# DS130-1_0-A_G-M.net
KiCad netlist of a schematic drawn in Altium Designer
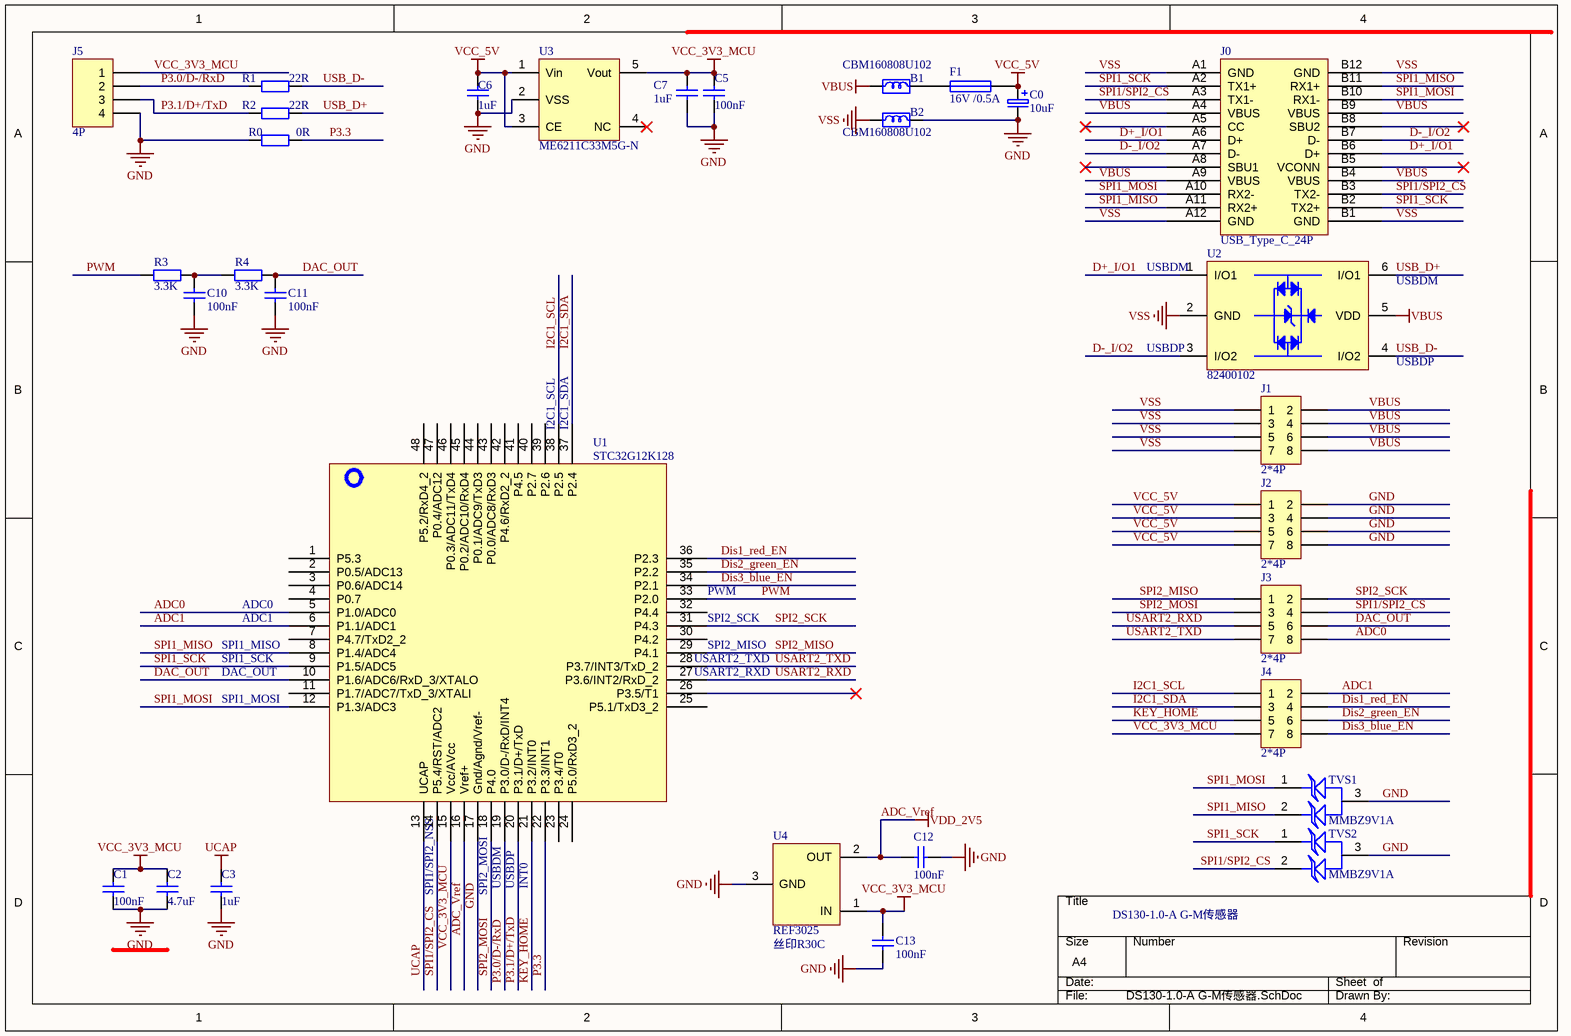
[diagram p0: DS130-1.0-A G-M传感器.SchDoc]

(export (version "E")
  (design (tool "Eeschema 10.0.6"))
  (components
    (comp (ref "B1")
      (value "CBM160808U102")
      (footprint "0603Bead")
      (description "贴片磁珠")
      (libsource (lib "AD_SCH") (part "Chip Ferrite Bead 0606"))
    )
    (comp (ref "B2")
      (value "CBM160808U102")
      (footprint "0603Bead")
      (description "贴片磁珠")
      (libsource (lib "AD_SCH") (part "Chip Ferrite Bead 0606"))
    )
    (comp (ref "C0")
      (value "10uF")
      (footprint "AVX_3216-18(1206)_SMD")
      (description "钽电容")
      (fields (field (name "Comment") "AVX_10uF/16V ±10％(C106)"))
      (libsource (lib "AD_SCH") (part "AVX_10uF/16V ±10％(C106)"))
    )
    (comp (ref "C1")
      (value "100nF")
      (footprint "0603CAP")
      (description "贴片电容")
      (fields (field (name "Comment") "SMDCAP00013"))
      (libsource (lib "AD_SCH") (part "MLCC 100nF 50V ±10％ 0603"))
    )
    (comp (ref "C2")
      (value "4.7uF")
      (footprint "0603CAP")
      (description "贴片电容")
      (fields (field (name "Comment") "SMDCAP00012"))
      (libsource (lib "AD_SCH") (part "MLCC 4.7uF 50V ±10％ 0603"))
    )
    (comp (ref "C3")
      (value "1uF")
      (footprint "0603CAP")
      (description "贴片电容")
      (fields (field (name "Comment") "SMDCAP00015"))
      (libsource (lib "AD_SCH") (part "MLCC 1uF 50V ±10％ 0603"))
    )
    (comp (ref "C5")
      (value "100nF")
      (footprint "0603CAP")
      (description "贴片电容")
      (fields (field (name "Comment") "SMDCAP00013"))
      (libsource (lib "AD_SCH") (part "MLCC 100nF 50V ±10％ 0603"))
    )
    (comp (ref "C6")
      (value "1uF")
      (footprint "0603CAP")
      (description "贴片电容")
      (fields (field (name "Comment") "SMDCAP00015"))
      (libsource (lib "AD_SCH") (part "MLCC 1uF 50V ±10％ 0603"))
    )
    (comp (ref "C7")
      (value "1uF")
      (footprint "0603CAP")
      (description "贴片电容")
      (fields (field (name "Comment") "SMDCAP00015"))
      (libsource (lib "AD_SCH") (part "MLCC 1uF 50V ±10％ 0603"))
    )
    (comp (ref "C10")
      (value "100nF")
      (footprint "0603CAP")
      (description "贴片电容")
      (fields (field (name "Comment") "SMDCAP00013"))
      (libsource (lib "AD_SCH") (part "MLCC 100nF 50V ±10％ 0603"))
    )
    (comp (ref "C11")
      (value "100nF")
      (footprint "0603CAP")
      (description "贴片电容")
      (fields (field (name "Comment") "SMDCAP00013"))
      (libsource (lib "AD_SCH") (part "MLCC 100nF 50V ±10％ 0603"))
    )
    (comp (ref "C12")
      (value "100nF")
      (footprint "0603CAP")
      (description "贴片电容")
      (fields (field (name "Comment") "SMDCAP00013"))
      (libsource (lib "AD_SCH") (part "MLCC 100nF 50V ±10％ 0603"))
    )
    (comp (ref "C13")
      (value "100nF")
      (footprint "0603CAP")
      (description "贴片电容")
      (fields (field (name "Comment") "SMDCAP00013"))
      (libsource (lib "AD_SCH") (part "MLCC 100nF 50V ±10％ 0603"))
    )
    (comp (ref "F1")
      (value "16V /0.5A")
      (footprint "1206FUSE")
      (description "贴片自恢复保险丝 16V /0.5A")
      (fields (field (name "Comment") "SMD1206-050C-16V"))
      (libsource (lib "AD_SCH") (part "SMD1206-050C-16V"))
    )
    (comp (ref "J0")
      (value "USB_Type_C_24P")
      (footprint "USB_TYPE_C_24P_Receptacle")
      (libsource (lib "AD_SCH") (part "USB_Type_C_24P"))
    )
    (comp (ref "J1")
      (value "2*4P")
      (footprint "X1321FVS-2x04-C43D48")
      (description "双排母2x4P 立贴 1.27mm")
      (fields (field (name "Comment") "X1321FVS-2x04-C43D48"))
      (libsource (lib "AD_SCH") (part "X1321FVS-2x04-C43D48"))
    )
    (comp (ref "J2")
      (value "2*4P")
      (footprint "X1321FVS-2x04-C43D48")
      (description "双排母2x4P 立贴 1.27mm")
      (fields (field (name "Comment") "X1321FVS-2x04-C43D48"))
      (libsource (lib "AD_SCH") (part "X1321FVS-2x04-C43D48"))
    )
    (comp (ref "J3")
      (value "2*4P")
      (footprint "X1321FVS-2x04-C43D48")
      (description "双排母2x4P 立贴 1.27mm")
      (fields (field (name "Comment") "X1321FVS-2x04-C43D48"))
      (libsource (lib "AD_SCH") (part "X1321FVS-2x04-C43D48"))
    )
    (comp (ref "J4")
      (value "2*4P")
      (footprint "X1321FVS-2x04-C43D48")
      (description "双排母2x4P 立贴 1.27mm")
      (fields (field (name "Comment") "X1321FVS-2x04-C43D48"))
      (libsource (lib "AD_SCH") (part "X1321FVS-2x04-C43D48"))
    )
    (comp (ref "J5")
      (value "4P")
      (footprint "H4")
      (description "单排直针")
      (fields (field (name "Comment") "DIP4单排直针  间距2mm 针长11mm 铜"))
      (libsource (lib "AD_SCH") (part "DIP4单排直针  间距2mm 针长11mm 铜"))
    )
    (comp (ref "R0")
      (value "0R")
      (footprint "0603RES")
      (description "贴片电阻")
      (fields (field (name "Comment") "Chip 0R 1/16W ±1％ 0603"))
      (libsource (lib "AD_SCH") (part "Chip 0R 1/16W ±1％ 0603"))
    )
    (comp (ref "R1")
      (value "22R")
      (footprint "0603RES")
      (description "贴片电阻")
      (fields (field (name "Comment") "Chip 22R 1/16W ±1％ 0603"))
      (libsource (lib "AD_SCH") (part "Chip 22R 1/16W ±1％ 0603"))
    )
    (comp (ref "R2")
      (value "22R")
      (footprint "0603RES")
      (description "贴片电阻")
      (fields (field (name "Comment") "Chip 22R 1/16W ±1％ 0603"))
      (libsource (lib "AD_SCH") (part "Chip 22R 1/16W ±1％ 0603"))
    )
    (comp (ref "R3")
      (value "3.3K")
      (footprint "0603RES")
      (description "贴片电阻")
      (fields (field (name "Comment") "SMDRES00090"))
      (libsource (lib "AD_SCH") (part "Chip 3.3K 1/16W ±1％ 0603"))
    )
    (comp (ref "R4")
      (value "3.3K")
      (footprint "0603RES")
      (description "贴片电阻")
      (fields (field (name "Comment") "SMDRES00090"))
      (libsource (lib "AD_SCH") (part "Chip 3.3K 1/16W ±1％ 0603"))
    )
    (comp (ref "TVS1")
      (value "MMBZ9V1A")
      (footprint "SOT23")
      (description "瞬态抑制二极管")
      (libsource (lib "AD_SCH") (part "TVS"))
    )
    (comp (ref "TVS2")
      (value "MMBZ9V1A")
      (footprint "SOT23")
      (description "瞬态抑制二极管")
      (libsource (lib "AD_SCH") (part "TVS"))
    )
    (comp (ref "U1")
      (value "STC32G12K128")
      (footprint "LQFP-48")
      (description "单片机芯片")
      (fields (field (name "Comment") "STC32G12K128_35I LQFP48"))
      (libsource (lib "AD_SCH") (part "STC32G12K128_35I LQFP48"))
    )
    (comp (ref "U2")
      (value "82400102")
      (footprint "SOT23-6")
      (description "瞬态抑制二极管(TVS)")
      (libsource (lib "AD_SCH") (part "82400102"))
    )
    (comp (ref "U3")
      (value "ME6211C33M5G-N")
      (footprint "SOT23-5")
      (description "稳压芯片")
      (libsource (lib "AD_SCH") (part "ME6211C33M5G-N"))
    )
    (comp (ref "U4")
      (value "REF3025")
      (footprint "SOT23")
      (fields (field (name "ALTIUM_VALUE") "丝印R30C"))
      (libsource (lib "AD_SCH") (part "REF3025"))
    )
  )
  (nets
    (net (code "1") (name "/ADC0") (class "Default")
      (node (ref "J3") (pin "8") (pinfunction "8_8") (pintype "passive"))
      (node (ref "U1") (pin "5") (pinfunction "P1.0/ADC0_5") (pintype "passive"))
    )
    (net (code "2") (name "/ADC1") (class "Default")
      (node (ref "J4") (pin "2") (pinfunction "2_2") (pintype "passive"))
      (node (ref "U1") (pin "6") (pinfunction "P1.1/ADC1_6") (pintype "passive"))
    )
    (net (code "3") (name "/D+_I{slash}O1") (class "Default")
      (node (ref "J0") (pin "A6") (pinfunction "D+_A6") (pintype "passive"))
      (node (ref "J0") (pin "B6") (pinfunction "D+_B6") (pintype "passive"))
      (node (ref "U2") (pin "1") (pinfunction "I/O1_1") (pintype "passive"))
    )
    (net (code "4") (name "/D-_I{slash}O2") (class "Default")
      (node (ref "J0") (pin "A7") (pinfunction "D-_A7") (pintype "passive"))
      (node (ref "J0") (pin "B7") (pinfunction "D-_B7") (pintype "passive"))
      (node (ref "U2") (pin "3") (pinfunction "I/O2_3") (pintype "passive"))
    )
    (net (code "5") (name "/DAC_OUT") (class "Default")
      (node (ref "C11") (pin "2") (pinfunction "2_2") (pintype "passive"))
      (node (ref "J3") (pin "6") (pinfunction "6_6") (pintype "passive"))
      (node (ref "R4") (pin "2") (pinfunction "2_2") (pintype "passive"))
      (node (ref "U1") (pin "10") (pinfunction "P1.6/ADC6/RxD_3/XTALO_10") (pintype "passive"))
    )
    (net (code "6") (name "/Dis1_red_EN") (class "Default")
      (node (ref "J4") (pin "4") (pinfunction "4_4") (pintype "passive"))
      (node (ref "U1") (pin "36") (pinfunction "P2.3_36") (pintype "passive"))
    )
    (net (code "7") (name "/Dis2_green_EN") (class "Default")
      (node (ref "J4") (pin "6") (pinfunction "6_6") (pintype "passive"))
      (node (ref "U1") (pin "35") (pinfunction "P2.2_35") (pintype "passive"))
    )
    (net (code "8") (name "/Dis3_blue_EN") (class "Default")
      (node (ref "J4") (pin "8") (pinfunction "8_8") (pintype "passive"))
      (node (ref "U1") (pin "34") (pinfunction "P2.1_34") (pintype "passive"))
    )
    (net (code "9") (name "/I2C1_SCL") (class "Default")
      (node (ref "J4") (pin "1") (pinfunction "1_1") (pintype "passive"))
      (node (ref "U1") (pin "38") (pinfunction "P2.5_38") (pintype "passive"))
    )
    (net (code "10") (name "/I2C1_SDA") (class "Default")
      (node (ref "J4") (pin "3") (pinfunction "3_3") (pintype "passive"))
      (node (ref "U1") (pin "37") (pinfunction "P2.4_37") (pintype "passive"))
    )
    (net (code "11") (name "/KEY_HOME") (class "Default")
      (node (ref "J4") (pin "5") (pinfunction "5_5") (pintype "passive"))
      (node (ref "U1") (pin "21") (pinfunction "P3.2/INT0_21") (pintype "passive"))
    )
    (net (code "12") (name "/P3.0{slash}D-{slash}RxD") (class "Default")
      (node (ref "J5") (pin "2") (pinfunction "2_2") (pintype "passive"))
      (node (ref "R1") (pin "1") (pinfunction "1_1") (pintype "passive"))
      (node (ref "U1") (pin "19") (pinfunction "P3.0/D-/RxD/INT4_19") (pintype "passive"))
    )
    (net (code "13") (name "/P3.1{slash}D+{slash}TxD") (class "Default")
      (node (ref "J5") (pin "3") (pinfunction "3_3") (pintype "passive"))
      (node (ref "R2") (pin "1") (pinfunction "1_1") (pintype "passive"))
      (node (ref "U1") (pin "20") (pinfunction "P3.1/D+/TxD_20") (pintype "passive"))
    )
    (net (code "14") (name "/P3.3") (class "Default")
      (node (ref "R0") (pin "2") (pinfunction "2_2") (pintype "passive"))
      (node (ref "U1") (pin "22") (pinfunction "P3.3/INT1_22") (pintype "passive"))
    )
    (net (code "15") (name "/PWM") (class "Default")
      (node (ref "R3") (pin "1") (pinfunction "1_1") (pintype "passive"))
      (node (ref "U1") (pin "33") (pinfunction "P2.0_33") (pintype "passive"))
    )
    (net (code "16") (name "/SPI1_MISO") (class "Default")
      (node (ref "J0") (pin "A11") (pinfunction "RX2+_A11") (pintype "passive"))
      (node (ref "J0") (pin "B11") (pinfunction "RX1+_B11") (pintype "passive"))
      (node (ref "TVS1") (pin "2") (pinfunction "2_2") (pintype "passive"))
      (node (ref "U1") (pin "8") (pinfunction "P1.4/ADC4_8") (pintype "passive"))
    )
    (net (code "17") (name "/SPI1_MOSI") (class "Default")
      (node (ref "J0") (pin "A10") (pinfunction "RX2-_A10") (pintype "passive"))
      (node (ref "J0") (pin "B10") (pinfunction "RX1-_B10") (pintype "passive"))
      (node (ref "TVS1") (pin "1") (pinfunction "1_1") (pintype "passive"))
      (node (ref "U1") (pin "12") (pinfunction "P1.3/ADC3_12") (pintype "passive"))
    )
    (net (code "18") (name "/SPI1_SCK") (class "Default")
      (node (ref "J0") (pin "A2") (pinfunction "TX1+_A2") (pintype "passive"))
      (node (ref "J0") (pin "B2") (pinfunction "TX2+_B2") (pintype "passive"))
      (node (ref "TVS2") (pin "1") (pinfunction "1_1") (pintype "passive"))
      (node (ref "U1") (pin "9") (pinfunction "P1.5/ADC5_9") (pintype "passive"))
    )
    (net (code "19") (name "/SPI1{slash}SPI2_CS") (class "Default")
      (node (ref "J0") (pin "A3") (pinfunction "TX1-_A3") (pintype "passive"))
      (node (ref "J0") (pin "B3") (pinfunction "TX2-_B3") (pintype "passive"))
      (node (ref "J3") (pin "4") (pinfunction "4_4") (pintype "passive"))
      (node (ref "TVS2") (pin "2") (pinfunction "2_2") (pintype "passive"))
      (node (ref "U1") (pin "14") (pinfunction "P5.4/RST/ADC2_14") (pintype "passive"))
    )
    (net (code "20") (name "/SPI2_MISO") (class "Default")
      (node (ref "J3") (pin "1") (pinfunction "1_1") (pintype "passive"))
      (node (ref "U1") (pin "29") (pinfunction "P4.1_29") (pintype "passive"))
    )
    (net (code "21") (name "/SPI2_MOSI") (class "Default")
      (node (ref "J3") (pin "3") (pinfunction "3_3") (pintype "passive"))
      (node (ref "U1") (pin "18") (pinfunction "P4.0_18") (pintype "passive"))
    )
    (net (code "22") (name "/SPI2_SCK") (class "Default")
      (node (ref "J3") (pin "2") (pinfunction "2_2") (pintype "passive"))
      (node (ref "U1") (pin "31") (pinfunction "P4.3_31") (pintype "passive"))
    )
    (net (code "23") (name "/USART2_RXD") (class "Default")
      (node (ref "J3") (pin "5") (pinfunction "5_5") (pintype "passive"))
      (node (ref "U1") (pin "27") (pinfunction "P3.6/INT2/RxD_2_27") (pintype "passive"))
    )
    (net (code "24") (name "/USART2_TXD") (class "Default")
      (node (ref "J3") (pin "7") (pinfunction "7_7") (pintype "passive"))
      (node (ref "U1") (pin "28") (pinfunction "P3.7/INT3/TxD_2_28") (pintype "passive"))
    )
    (net (code "25") (name "/USB_D+") (class "Default")
      (node (ref "R2") (pin "2") (pinfunction "2_2") (pintype "passive"))
      (node (ref "U2") (pin "6") (pinfunction "I/O1_6") (pintype "passive"))
    )
    (net (code "26") (name "/USB_D-") (class "Default")
      (node (ref "R1") (pin "2") (pinfunction "2_2") (pintype "passive"))
      (node (ref "U2") (pin "4") (pinfunction "I/O2_4") (pintype "passive"))
    )
    (net (code "27") (name "GND") (class "Default")
      (node (ref "B2") (pin "2") (pinfunction "2_2") (pintype "passive"))
      (node (ref "C0") (pin "2") (pinfunction "2_2") (pintype "passive"))
      (node (ref "C1") (pin "1") (pinfunction "1_1") (pintype "passive"))
      (node (ref "C10") (pin "1") (pinfunction "1_1") (pintype "passive"))
      (node (ref "C11") (pin "1") (pinfunction "1_1") (pintype "passive"))
      (node (ref "C12") (pin "1") (pinfunction "1_1") (pintype "passive"))
      (node (ref "C13") (pin "1") (pinfunction "1_1") (pintype "passive"))
      (node (ref "C2") (pin "1") (pinfunction "1_1") (pintype "passive"))
      (node (ref "C3") (pin "1") (pinfunction "1_1") (pintype "passive"))
      (node (ref "C5") (pin "1") (pinfunction "1_1") (pintype "passive"))
      (node (ref "C6") (pin "1") (pinfunction "1_1") (pintype "passive"))
      (node (ref "C7") (pin "1") (pinfunction "1_1") (pintype "passive"))
      (node (ref "J2") (pin "2") (pinfunction "2_2") (pintype "passive"))
      (node (ref "J2") (pin "4") (pinfunction "4_4") (pintype "passive"))
      (node (ref "J2") (pin "6") (pinfunction "6_6") (pintype "passive"))
      (node (ref "J2") (pin "8") (pinfunction "8_8") (pintype "passive"))
      (node (ref "J5") (pin "4") (pinfunction "4_4") (pintype "passive"))
      (node (ref "R0") (pin "1") (pinfunction "1_1") (pintype "passive"))
      (node (ref "TVS1") (pin "3") (pinfunction "3_3") (pintype "passive"))
      (node (ref "TVS2") (pin "3") (pinfunction "3_3") (pintype "passive"))
      (node (ref "U1") (pin "17") (pinfunction "Gnd/Agnd/Vref-_17") (pintype "passive"))
      (node (ref "U3") (pin "2") (pinfunction "VSS_2") (pintype "passive"))
      (node (ref "U4") (pin "3") (pinfunction "GND_3") (pintype "passive"))
    )
    (net (code "28") (name "Net-(B1-Pad2)") (class "Default")
      (node (ref "B1") (pin "2") (pinfunction "2_2") (pintype "passive"))
      (node (ref "F1") (pin "1") (pinfunction "1_1") (pintype "passive"))
    )
    (net (code "29") (name "Net-(C10-Pad2)") (class "Default")
      (node (ref "C10") (pin "2") (pinfunction "2_2") (pintype "passive"))
      (node (ref "R3") (pin "2") (pinfunction "2_2") (pintype "passive"))
      (node (ref "R4") (pin "1") (pinfunction "1_1") (pintype "passive"))
    )
    (net (code "30") (name "UCAP") (class "Default")
      (node (ref "C3") (pin "2") (pinfunction "2_2") (pintype "passive"))
      (node (ref "U1") (pin "13") (pinfunction "UCAP_13") (pintype "passive"))
    )
    (net (code "31") (name "VBUS") (class "Default")
      (node (ref "B1") (pin "1") (pinfunction "1_1") (pintype "passive"))
      (node (ref "J0") (pin "A4") (pinfunction "VBUS_A4") (pintype "passive"))
      (node (ref "J0") (pin "A9") (pinfunction "VBUS_A9") (pintype "passive"))
      (node (ref "J0") (pin "B4") (pinfunction "VBUS_B4") (pintype "passive"))
      (node (ref "J0") (pin "B9") (pinfunction "VBUS_B9") (pintype "passive"))
      (node (ref "J1") (pin "2") (pinfunction "2_2") (pintype "passive"))
      (node (ref "J1") (pin "4") (pinfunction "4_4") (pintype "passive"))
      (node (ref "J1") (pin "6") (pinfunction "6_6") (pintype "passive"))
      (node (ref "J1") (pin "8") (pinfunction "8_8") (pintype "passive"))
      (node (ref "U2") (pin "5") (pinfunction "VDD_5") (pintype "passive"))
    )
    (net (code "32") (name "VCC_3V3_MCU") (class "Default")
      (node (ref "C1") (pin "2") (pinfunction "2_2") (pintype "passive"))
      (node (ref "C13") (pin "2") (pinfunction "2_2") (pintype "passive"))
      (node (ref "C2") (pin "2") (pinfunction "2_2") (pintype "passive"))
      (node (ref "C5") (pin "2") (pinfunction "2_2") (pintype "passive"))
      (node (ref "C7") (pin "2") (pinfunction "2_2") (pintype "passive"))
      (node (ref "J4") (pin "7") (pinfunction "7_7") (pintype "passive"))
      (node (ref "J5") (pin "1") (pinfunction "1_1") (pintype "passive"))
      (node (ref "U1") (pin "15") (pinfunction "Vcc/AVcc_15") (pintype "passive"))
      (node (ref "U3") (pin "5") (pinfunction "Vout_5") (pintype "passive"))
      (node (ref "U4") (pin "1") (pinfunction "IN_1") (pintype "passive"))
    )
    (net (code "33") (name "VCC_5V") (class "Default")
      (node (ref "C0") (pin "1") (pinfunction "1_1") (pintype "passive"))
      (node (ref "C6") (pin "2") (pinfunction "2_2") (pintype "passive"))
      (node (ref "F1") (pin "2") (pinfunction "2_2") (pintype "passive"))
      (node (ref "J2") (pin "1") (pinfunction "1_1") (pintype "passive"))
      (node (ref "J2") (pin "3") (pinfunction "3_3") (pintype "passive"))
      (node (ref "J2") (pin "5") (pinfunction "5_5") (pintype "passive"))
      (node (ref "J2") (pin "7") (pinfunction "7_7") (pintype "passive"))
      (node (ref "U3") (pin "1") (pinfunction "Vin_1") (pintype "passive"))
      (node (ref "U3") (pin "3") (pinfunction "CE_3") (pintype "passive"))
    )
    (net (code "34") (name "VDD_2V5") (class "Default")
      (node (ref "C12") (pin "2") (pinfunction "2_2") (pintype "passive"))
      (node (ref "U1") (pin "16") (pinfunction "Vref+_16") (pintype "passive"))
      (node (ref "U4") (pin "2") (pinfunction "OUT_2") (pintype "passive"))
    )
    (net (code "35") (name "VSS") (class "Default")
      (node (ref "B2") (pin "1") (pinfunction "1_1") (pintype "passive"))
      (node (ref "J0") (pin "A1") (pinfunction "GND_A1") (pintype "passive"))
      (node (ref "J0") (pin "A12") (pinfunction "GND_A12") (pintype "passive"))
      (node (ref "J0") (pin "B1") (pinfunction "GND_B1") (pintype "passive"))
      (node (ref "J0") (pin "B12") (pinfunction "GND_B12") (pintype "passive"))
      (node (ref "J1") (pin "1") (pinfunction "1_1") (pintype "passive"))
      (node (ref "J1") (pin "3") (pinfunction "3_3") (pintype "passive"))
      (node (ref "J1") (pin "5") (pinfunction "5_5") (pintype "passive"))
      (node (ref "J1") (pin "7") (pinfunction "7_7") (pintype "passive"))
      (node (ref "U2") (pin "2") (pinfunction "GND_2") (pintype "passive"))
    )
    (net (code "36") (name "unconnected-(J0-CC-PadA5)") (class "Default")
      (node (ref "J0") (pin "A5") (pinfunction "CC_A5") (pintype "passive+no_connect"))
    )
    (net (code "37") (name "unconnected-(J0-SBU1-PadA8)") (class "Default")
      (node (ref "J0") (pin "A8") (pinfunction "SBU1_A8") (pintype "passive+no_connect"))
    )
    (net (code "38") (name "unconnected-(J0-SBU2-PadB8)") (class "Default")
      (node (ref "J0") (pin "B8") (pinfunction "SBU2_B8") (pintype "passive+no_connect"))
    )
    (net (code "39") (name "unconnected-(J0-VCONN-PadB5)") (class "Default")
      (node (ref "J0") (pin "B5") (pinfunction "VCONN_B5") (pintype "passive+no_connect"))
    )
    (net (code "40") (name "unconnected-(U1-P0.0{slash}ADC8{slash}RxD3-Pad43)") (class "Default")
      (node (ref "U1") (pin "43") (pinfunction "P0.0/ADC8/RxD3_43") (pintype "passive"))
    )
    (net (code "41") (name "unconnected-(U1-P0.1{slash}ADC9{slash}TxD3-Pad44)") (class "Default")
      (node (ref "U1") (pin "44") (pinfunction "P0.1/ADC9/TxD3_44") (pintype "passive"))
    )
    (net (code "42") (name "unconnected-(U1-P0.2{slash}ADC10{slash}RxD4-Pad45)") (class "Default")
      (node (ref "U1") (pin "45") (pinfunction "P0.2/ADC10/RxD4_45") (pintype "passive"))
    )
    (net (code "43") (name "unconnected-(U1-P0.3{slash}ADC11{slash}TxD4-Pad46)") (class "Default")
      (node (ref "U1") (pin "46") (pinfunction "P0.3/ADC11/TxD4_46") (pintype "passive"))
    )
    (net (code "44") (name "unconnected-(U1-P0.4{slash}ADC12-Pad47)") (class "Default")
      (node (ref "U1") (pin "47") (pinfunction "P0.4/ADC12_47") (pintype "passive"))
    )
    (net (code "45") (name "unconnected-(U1-P0.5{slash}ADC13-Pad2)") (class "Default")
      (node (ref "U1") (pin "2") (pinfunction "P0.5/ADC13_2") (pintype "passive"))
    )
    (net (code "46") (name "unconnected-(U1-P0.6{slash}ADC14-Pad3)") (class "Default")
      (node (ref "U1") (pin "3") (pinfunction "P0.6/ADC14_3") (pintype "passive"))
    )
    (net (code "47") (name "unconnected-(U1-P0.7-Pad4)") (class "Default")
      (node (ref "U1") (pin "4") (pinfunction "P0.7_4") (pintype "passive"))
    )
    (net (code "48") (name "unconnected-(U1-P1.7{slash}ADC7{slash}TxD_3{slash}XTALI-Pad11)") (class "Default")
      (node (ref "U1") (pin "11") (pinfunction "P1.7/ADC7/TxD_3/XTALI_11") (pintype "passive"))
    )
    (net (code "49") (name "unconnected-(U1-P2.6-Pad39)") (class "Default")
      (node (ref "U1") (pin "39") (pinfunction "P2.6_39") (pintype "passive"))
    )
    (net (code "50") (name "unconnected-(U1-P2.7-Pad40)") (class "Default")
      (node (ref "U1") (pin "40") (pinfunction "P2.7_40") (pintype "passive"))
    )
    (net (code "51") (name "unconnected-(U1-P3.4{slash}T0-Pad23)") (class "Default")
      (node (ref "U1") (pin "23") (pinfunction "P3.4/T0_23") (pintype "passive"))
    )
    (net (code "52") (name "unconnected-(U1-P3.5{slash}T1-Pad26)") (class "Default")
      (node (ref "U1") (pin "26") (pinfunction "P3.5/T1_26") (pintype "passive+no_connect"))
    )
    (net (code "53") (name "unconnected-(U1-P4.2-Pad30)") (class "Default")
      (node (ref "U1") (pin "30") (pinfunction "P4.2_30") (pintype "passive"))
    )
    (net (code "54") (name "unconnected-(U1-P4.4-Pad32)") (class "Default")
      (node (ref "U1") (pin "32") (pinfunction "P4.4_32") (pintype "passive"))
    )
    (net (code "55") (name "unconnected-(U1-P4.5-Pad41)") (class "Default")
      (node (ref "U1") (pin "41") (pinfunction "P4.5_41") (pintype "passive"))
    )
    (net (code "56") (name "unconnected-(U1-P4.6{slash}RxD2_2-Pad42)") (class "Default")
      (node (ref "U1") (pin "42") (pinfunction "P4.6/RxD2_2_42") (pintype "passive"))
    )
    (net (code "57") (name "unconnected-(U1-P4.7{slash}TxD2_2-Pad7)") (class "Default")
      (node (ref "U1") (pin "7") (pinfunction "P4.7/TxD2_2_7") (pintype "passive"))
    )
    (net (code "58") (name "unconnected-(U1-P5.0{slash}RxD3_2-Pad24)") (class "Default")
      (node (ref "U1") (pin "24") (pinfunction "P5.0/RxD3_2_24") (pintype "passive"))
    )
    (net (code "59") (name "unconnected-(U1-P5.1{slash}TxD3_2-Pad25)") (class "Default")
      (node (ref "U1") (pin "25") (pinfunction "P5.1/TxD3_2_25") (pintype "passive"))
    )
    (net (code "60") (name "unconnected-(U1-P5.2{slash}RxD4_2-Pad48)") (class "Default")
      (node (ref "U1") (pin "48") (pinfunction "P5.2/RxD4_2_48") (pintype "passive"))
    )
    (net (code "61") (name "unconnected-(U1-P5.3-Pad1)") (class "Default")
      (node (ref "U1") (pin "1") (pinfunction "P5.3_1") (pintype "passive"))
    )
    (net (code "62") (name "unconnected-(U3-NC-Pad4)") (class "Default")
      (node (ref "U3") (pin "4") (pinfunction "NC_4") (pintype "passive+no_connect"))
    )
  )
)
